# 06_USB-UART_Bridge.net
KiCad netlist of a schematic drawn in Altium Designer
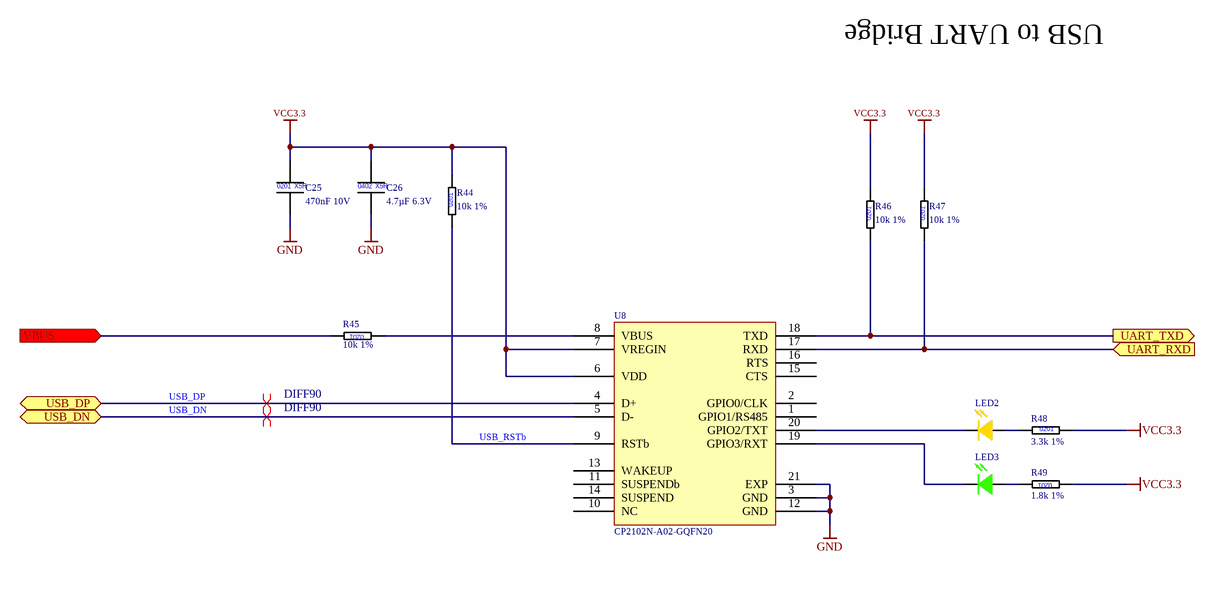
[diagram p0: 06_USB-UART Bridge.SchDoc]

(export (version "E")
  (design (tool "Eeschema 10.0.6"))
  (components
    (comp (ref "C25")
      (value "470nF 10V")
      (footprint "Zynq-Feather-HD:CAPC0603X03L")
      (description "Multilayer Ceramic Capacitors MLCC - SMD/SMT 0201 10VDC")
      (libsource (lib "Zynq-Feather-HD") (part "CAP_0201_470nF_10V"))
    )
    (comp (ref "C26")
      (value "4.7µF 6.3V")
      (footprint "Zynq-Feather-HD:CAPC1005X06L")
      (description "Multilayer Ceramic Capacitors MLCC - SMD/SMT 0402 6.3VDC")
      (libsource (lib "Zynq-Feather-HD") (part "CAP_0402_4.7µ_6.3V"))
    )
    (comp (ref "LED2")
      (value "150040YS73220")
      (footprint "Zynq-Feather-HD:WL-SMCC_0402_H=0.25mm")
      (description "Standard LEDs - SMD WL-SMCC SMT LED Mono-color")
      (libsource (lib "Zynq-Feather-HD") (part "150040YS73220_SMD WL-SMCC SMT LED Mono-color"))
    )
    (comp (ref "LED3")
      (value "150040GS73220")
      (footprint "Zynq-Feather-HD:WL-SMCC_0402_H=0.25mm")
      (description "Standard LEDs - SMD WL-SMCC SMT LED Mono-color")
      (libsource (lib "Zynq-Feather-HD") (part "150040GS73220_SMD WL-SMCC SMT LED Mono-color"))
    )
    (comp (ref "R44")
      (value "10k 1%")
      (footprint "Zynq-Feather-HD:RESC0603X03L")
      (description "Thick Film Resistors - SMD 10K OHM 1%")
      (libsource (lib "Zynq-Feather-HD") (part "RES_0201_10k_1%"))
    )
    (comp (ref "R45")
      (value "10k 1%")
      (footprint "Zynq-Feather-HD:RESC0603X03L")
      (description "Thick Film Resistors - SMD 10K OHM 1%")
      (libsource (lib "Zynq-Feather-HD") (part "RES_0201_10k_1%"))
    )
    (comp (ref "R46")
      (value "10k 1%")
      (footprint "Zynq-Feather-HD:RESC0603X03L")
      (description "Thick Film Resistors - SMD 10K OHM 1%")
      (libsource (lib "Zynq-Feather-HD") (part "RES_0201_10k_1%"))
    )
    (comp (ref "R47")
      (value "10k 1%")
      (footprint "Zynq-Feather-HD:RESC0603X03L")
      (description "Thick Film Resistors - SMD 10K OHM 1%")
      (libsource (lib "Zynq-Feather-HD") (part "RES_0201_10k_1%"))
    )
    (comp (ref "R48")
      (value "3.3k 1%")
      (footprint "Zynq-Feather-HD:RESC0603X03L")
      (description "Thick Film Resistors - SMD 3.3K OHM 1%")
      (libsource (lib "Zynq-Feather-HD") (part "RES_0201_3.3k_1%"))
    )
    (comp (ref "R49")
      (value "1.8k 1%")
      (footprint "Zynq-Feather-HD:RESC0603X03L")
      (description "Thick Film Resistors - SMD 1.8K OHM 1%")
      (libsource (lib "Zynq-Feather-HD") (part "RES_0201_1.8k_1%"))
    )
    (comp (ref "U8")
      (value "CP2102N-A02-GQFN20")
      (footprint "Zynq-Feather-HD:QFN50P300X300X80_HS-17L")
      (description "USB Interface IC USB to UART bridge - QFN20")
      (libsource (lib "Zynq-Feather-HD") (part "CP2102N-A02-GQFN20_USB Interface IC USB to UART bridge"))
    )
  )
  (nets
    (net (code "1") (name "/UART_RXD") (class "Default")
      (node (ref "R47") (pin "1") (pinfunction "1_1") (pintype "passive"))
      (node (ref "U8") (pin "17") (pinfunction "RXD_17") (pintype "passive"))
    )
    (net (code "2") (name "/UART_TXD") (class "Default")
      (node (ref "R46") (pin "1") (pinfunction "1_1") (pintype "passive"))
      (node (ref "U8") (pin "18") (pinfunction "TXD_18") (pintype "passive"))
    )
    (net (code "3") (name "/USB_DN") (class "Default")
      (node (ref "U8") (pin "5") (pinfunction "D-_5") (pintype "passive"))
    )
    (net (code "4") (name "/USB_DP") (class "Default")
      (node (ref "U8") (pin "4") (pinfunction "D+_4") (pintype "passive"))
    )
    (net (code "5") (name "/USB_RSTb") (class "Default")
      (node (ref "R44") (pin "1") (pinfunction "1_1") (pintype "passive"))
      (node (ref "U8") (pin "9") (pinfunction "RSTb_9") (pintype "passive"))
    )
    (net (code "6") (name "/VBUS") (class "Default")
      (node (ref "R45") (pin "2") (pinfunction "2_2") (pintype "passive"))
    )
    (net (code "7") (name "GND") (class "Default")
      (node (ref "C25") (pin "2") (pinfunction "2_2") (pintype "passive"))
      (node (ref "C26") (pin "2") (pinfunction "2_2") (pintype "passive"))
      (node (ref "U8") (pin "12") (pinfunction "GND_12") (pintype "passive"))
      (node (ref "U8") (pin "21") (pinfunction "EXP_21") (pintype "passive"))
      (node (ref "U8") (pin "3") (pinfunction "GND_3") (pintype "passive"))
    )
    (net (code "8") (name "Net-(LED2-Pad2)") (class "Default")
      (node (ref "LED2") (pin "2") (pinfunction "2_2") (pintype "passive"))
      (node (ref "R48") (pin "1") (pinfunction "1_1") (pintype "passive"))
    )
    (net (code "9") (name "Net-(LED3-Pad2)") (class "Default")
      (node (ref "LED3") (pin "2") (pinfunction "2_2") (pintype "passive"))
      (node (ref "R49") (pin "2") (pinfunction "2_2") (pintype "passive"))
    )
    (net (code "10") (name "Net-(U8-GPIO2{slash}TXT)") (class "Default")
      (node (ref "LED2") (pin "1") (pinfunction "1_1") (pintype "passive"))
      (node (ref "U8") (pin "20") (pinfunction "GPIO2/TXT_20") (pintype "passive"))
    )
    (net (code "11") (name "Net-(U8-GPIO3{slash}RXT)") (class "Default")
      (node (ref "LED3") (pin "1") (pinfunction "1_1") (pintype "passive"))
      (node (ref "U8") (pin "19") (pinfunction "GPIO3/RXT_19") (pintype "passive"))
    )
    (net (code "12") (name "Net-(U8-VBUS)") (class "Default")
      (node (ref "R45") (pin "1") (pinfunction "1_1") (pintype "passive"))
      (node (ref "U8") (pin "8") (pinfunction "VBUS_8") (pintype "passive"))
    )
    (net (code "13") (name "VCC3.3") (class "Default")
      (node (ref "C25") (pin "1") (pinfunction "1_1") (pintype "passive"))
      (node (ref "C26") (pin "1") (pinfunction "1_1") (pintype "passive"))
      (node (ref "R44") (pin "2") (pinfunction "2_2") (pintype "passive"))
      (node (ref "R46") (pin "2") (pinfunction "2_2") (pintype "passive"))
      (node (ref "R47") (pin "2") (pinfunction "2_2") (pintype "passive"))
      (node (ref "R48") (pin "2") (pinfunction "2_2") (pintype "passive"))
      (node (ref "R49") (pin "1") (pinfunction "1_1") (pintype "passive"))
      (node (ref "U8") (pin "6") (pinfunction "VDD_6") (pintype "passive"))
      (node (ref "U8") (pin "7") (pinfunction "VREGIN_7") (pintype "passive"))
    )
    (net (code "14") (name "unconnected-(U8-CTS-Pad15)") (class "Default")
      (node (ref "U8") (pin "15") (pinfunction "CTS_15") (pintype "passive"))
    )
    (net (code "15") (name "unconnected-(U8-GPIO0{slash}CLK-Pad2)") (class "Default")
      (node (ref "U8") (pin "2") (pinfunction "GPIO0/CLK_2") (pintype "passive"))
    )
    (net (code "16") (name "unconnected-(U8-GPIO1{slash}RS485-Pad1)") (class "Default")
      (node (ref "U8") (pin "1") (pinfunction "GPIO1/RS485_1") (pintype "passive"))
    )
    (net (code "17") (name "unconnected-(U8-NC-Pad10)") (class "Default")
      (node (ref "U8") (pin "10") (pinfunction "NC_10") (pintype "passive"))
    )
    (net (code "18") (name "unconnected-(U8-RTS-Pad16)") (class "Default")
      (node (ref "U8") (pin "16") (pinfunction "RTS_16") (pintype "passive"))
    )
    (net (code "19") (name "unconnected-(U8-SUSPEND-Pad14)") (class "Default")
      (node (ref "U8") (pin "14") (pinfunction "SUSPEND_14") (pintype "passive"))
    )
    (net (code "20") (name "unconnected-(U8-SUSPENDb-Pad11)") (class "Default")
      (node (ref "U8") (pin "11") (pinfunction "SUSPENDb_11") (pintype "passive"))
    )
    (net (code "21") (name "unconnected-(U8-WAKEUP-Pad13)") (class "Default")
      (node (ref "U8") (pin "13") (pinfunction "WAKEUP_13") (pintype "passive"))
    )
  )
)
